# NXT.net
KiCad netlist of a schematic drawn in EAGLE
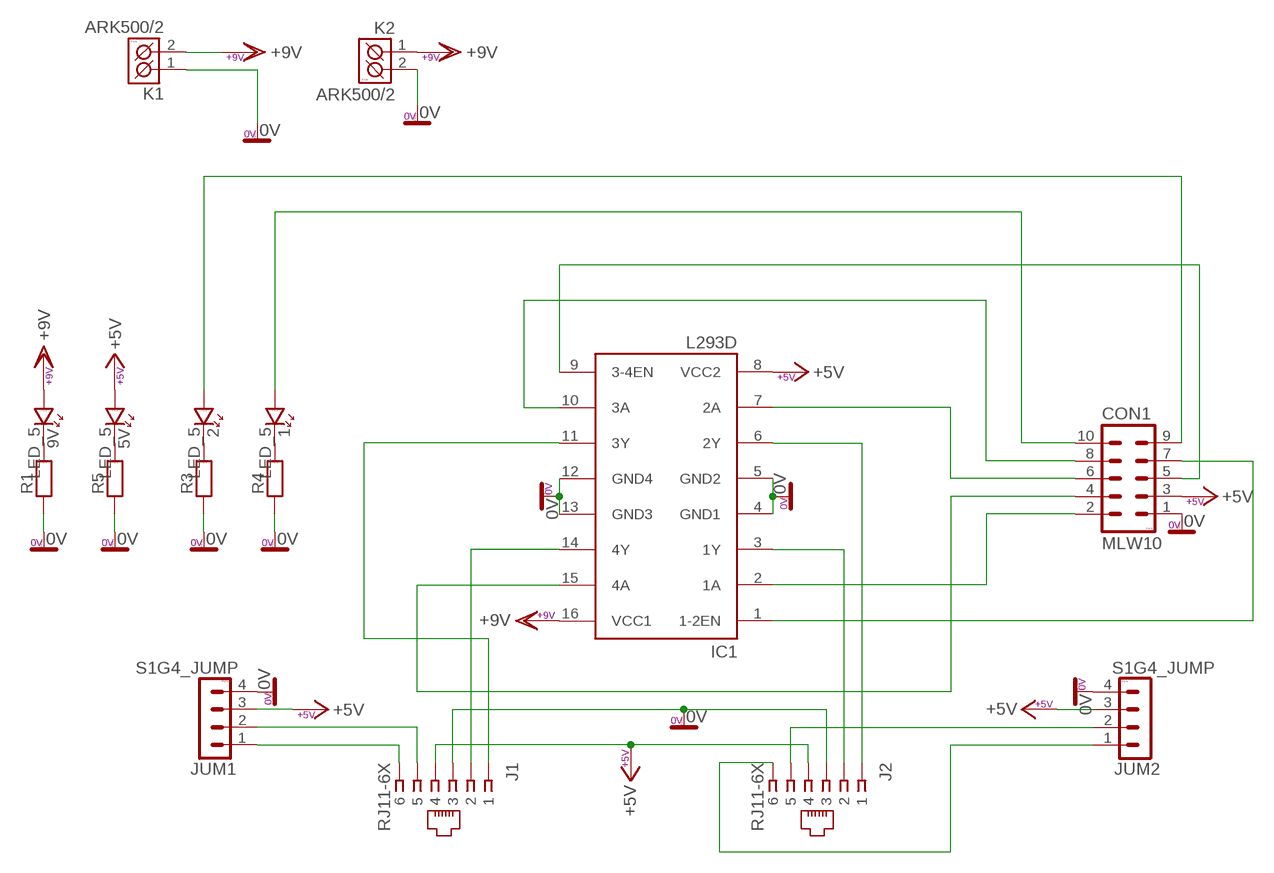
[diagram p0: schematic, sheet 1]

(export (version "E")
  (design (tool "Eeschema 10.0.6"))
  (components
    (comp (ref "1")
      (value "LED_5")
      (footprint "eagle-import:LED_5")
      (libsource (lib "eagle-import") (part "LED_5"))
    )
    (comp (ref "2")
      (value "LED_5")
      (footprint "eagle-import:LED_5")
      (libsource (lib "eagle-import") (part "LED_5"))
    )
    (comp (ref "5V")
      (value "LED_5")
      (footprint "eagle-import:LED_5")
      (libsource (lib "eagle-import") (part "LED_5"))
    )
    (comp (ref "9V")
      (value "LED_5")
      (footprint "eagle-import:LED_5")
      (libsource (lib "eagle-import") (part "LED_5"))
    )
    (comp (ref "CON1")
      (value "MLW10")
      (footprint "eagle-import:MLW10G")
      (libsource (lib "eagle-import") (part "MLW10"))
    )
    (comp (ref "IC1")
      (value "L293D")
      (footprint "eagle-import:DIL16")
      (libsource (lib "eagle-import") (part "L293D"))
    )
    (comp (ref "J1")
      (value "RJ11-6X")
      (footprint "eagle-import:RJ11-NO_SHIELD")
      (libsource (lib "eagle-import") (part "RJ11-6X"))
    )
    (comp (ref "J2")
      (value "RJ11-6X")
      (footprint "eagle-import:RJ11-NO_SHIELD")
      (libsource (lib "eagle-import") (part "RJ11-6X"))
    )
    (comp (ref "JUM1")
      (value "S1G4_JUMP")
      (footprint "eagle-import:S1G4_JUM")
      (libsource (lib "eagle-import") (part "S1G4_JUMP"))
    )
    (comp (ref "JUM2")
      (value "S1G4_JUMP")
      (footprint "eagle-import:S1G4_JUM")
      (libsource (lib "eagle-import") (part "S1G4_JUMP"))
    )
    (comp (ref "K1")
      (value "ARK500/2")
      (footprint "eagle-import:ARK500_2")
      (libsource (lib "eagle-import") (part "ARK500/2"))
    )
    (comp (ref "K2")
      (value "ARK500/2")
      (footprint "eagle-import:ARK500_2")
      (libsource (lib "eagle-import") (part "ARK500/2"))
    )
    (comp (ref "R1")
      (value "R_10")
      (footprint "eagle-import:R-10")
      (libsource (lib "eagle-import") (part "R_10"))
    )
    (comp (ref "R3")
      (value "R_10")
      (footprint "eagle-import:R-10")
      (libsource (lib "eagle-import") (part "R_10"))
    )
    (comp (ref "R4")
      (value "R_10")
      (footprint "eagle-import:R-10")
      (libsource (lib "eagle-import") (part "R_10"))
    )
    (comp (ref "R5")
      (value "R_10")
      (footprint "eagle-import:R-10")
      (libsource (lib "eagle-import") (part "R_10"))
    )
  )
  (nets
    (net (code "1") (name "+5V") (class "Default")
      (node (ref "5V") (pin "A") (pinfunction "A_A") (pintype "passive"))
      (node (ref "CON1") (pin "3") (pinfunction "3_3") (pintype "passive"))
      (node (ref "IC1") (pin "8") (pinfunction "VCC2_8") (pintype "power_in"))
      (node (ref "J1") (pin "4") (pinfunction "4_4") (pintype "passive"))
      (node (ref "J2") (pin "4") (pinfunction "4_4") (pintype "passive"))
      (node (ref "JUM1") (pin "3") (pinfunction "3_3") (pintype "passive"))
      (node (ref "JUM2") (pin "3") (pinfunction "3_3") (pintype "passive"))
    )
    (net (code "2") (name "+9V") (class "Default")
      (node (ref "9V") (pin "A") (pinfunction "A_A") (pintype "passive"))
      (node (ref "IC1") (pin "16") (pinfunction "VCC1_16") (pintype "power_in"))
      (node (ref "K1") (pin "2") (pinfunction "K2_2") (pintype "passive"))
      (node (ref "K2") (pin "1") (pinfunction "K1_1") (pintype "passive"))
    )
    (net (code "3") (name "0V") (class "Default")
      (node (ref "CON1") (pin "1") (pinfunction "1_1") (pintype "passive"))
      (node (ref "IC1") (pin "12") (pinfunction "GND4_12") (pintype "power_in"))
      (node (ref "IC1") (pin "13") (pinfunction "GND3_13") (pintype "power_in"))
      (node (ref "IC1") (pin "4") (pinfunction "GND1_4") (pintype "power_in"))
      (node (ref "IC1") (pin "5") (pinfunction "GND2_5") (pintype "power_in"))
      (node (ref "J1") (pin "3") (pinfunction "3_3") (pintype "passive"))
      (node (ref "J2") (pin "3") (pinfunction "3_3") (pintype "passive"))
      (node (ref "JUM1") (pin "4") (pinfunction "4_4") (pintype "passive"))
      (node (ref "JUM2") (pin "4") (pinfunction "4_4") (pintype "passive"))
      (node (ref "K1") (pin "1") (pinfunction "K1_1") (pintype "passive"))
      (node (ref "K2") (pin "2") (pinfunction "K2_2") (pintype "passive"))
      (node (ref "R1") (pin "1") (pinfunction "1_1") (pintype "passive"))
      (node (ref "R3") (pin "1") (pinfunction "1_1") (pintype "passive"))
      (node (ref "R4") (pin "1") (pinfunction "1_1") (pintype "passive"))
      (node (ref "R5") (pin "1") (pinfunction "1_1") (pintype "passive"))
    )
    (net (code "4") (name "Net-(1-PadA)") (class "Default")
      (node (ref "1") (pin "A") (pinfunction "A_A") (pintype "passive"))
      (node (ref "CON1") (pin "10") (pinfunction "10_10") (pintype "passive"))
    )
    (net (code "5") (name "Net-(1-PadK)") (class "Default")
      (node (ref "1") (pin "K") (pinfunction "K_K") (pintype "passive"))
      (node (ref "R4") (pin "2") (pinfunction "2_2") (pintype "passive"))
    )
    (net (code "6") (name "Net-(2-PadA)") (class "Default")
      (node (ref "2") (pin "A") (pinfunction "A_A") (pintype "passive"))
      (node (ref "CON1") (pin "9") (pinfunction "9_9") (pintype "passive"))
    )
    (net (code "7") (name "Net-(2-PadK)") (class "Default")
      (node (ref "2") (pin "K") (pinfunction "K_K") (pintype "passive"))
      (node (ref "R3") (pin "2") (pinfunction "2_2") (pintype "passive"))
    )
    (net (code "8") (name "Net-(5V-PadK)") (class "Default")
      (node (ref "5V") (pin "K") (pinfunction "K_K") (pintype "passive"))
      (node (ref "R5") (pin "2") (pinfunction "2_2") (pintype "passive"))
    )
    (net (code "9") (name "Net-(9V-PadK)") (class "Default")
      (node (ref "9V") (pin "K") (pinfunction "K_K") (pintype "passive"))
      (node (ref "R1") (pin "2") (pinfunction "2_2") (pintype "passive"))
    )
    (net (code "10") (name "Net-(IC1-1-2EN)") (class "Default")
      (node (ref "CON1") (pin "7") (pinfunction "7_7") (pintype "passive"))
      (node (ref "IC1") (pin "1") (pinfunction "1-2EN_1") (pintype "input"))
    )
    (net (code "11") (name "Net-(IC1-1A)") (class "Default")
      (node (ref "CON1") (pin "2") (pinfunction "2_2") (pintype "passive"))
      (node (ref "IC1") (pin "2") (pinfunction "1A_2") (pintype "input"))
    )
    (net (code "12") (name "Net-(IC1-1Y)") (class "Default")
      (node (ref "IC1") (pin "3") (pinfunction "1Y_3") (pintype "output"))
      (node (ref "J2") (pin "2") (pinfunction "2_2") (pintype "passive"))
    )
    (net (code "13") (name "Net-(IC1-2A)") (class "Default")
      (node (ref "CON1") (pin "6") (pinfunction "6_6") (pintype "passive"))
      (node (ref "IC1") (pin "7") (pinfunction "2A_7") (pintype "input"))
    )
    (net (code "14") (name "Net-(IC1-2Y)") (class "Default")
      (node (ref "IC1") (pin "6") (pinfunction "2Y_6") (pintype "output"))
      (node (ref "J2") (pin "1") (pinfunction "1_1") (pintype "passive"))
    )
    (net (code "15") (name "Net-(IC1-3-4EN)") (class "Default")
      (node (ref "CON1") (pin "5") (pinfunction "5_5") (pintype "passive"))
      (node (ref "IC1") (pin "9") (pinfunction "3-4EN_9") (pintype "input"))
    )
    (net (code "16") (name "Net-(IC1-3A)") (class "Default")
      (node (ref "CON1") (pin "8") (pinfunction "8_8") (pintype "passive"))
      (node (ref "IC1") (pin "10") (pinfunction "3A_10") (pintype "input"))
    )
    (net (code "17") (name "Net-(IC1-3Y)") (class "Default")
      (node (ref "IC1") (pin "11") (pinfunction "3Y_11") (pintype "output"))
      (node (ref "J1") (pin "1") (pinfunction "1_1") (pintype "passive"))
    )
    (net (code "18") (name "Net-(IC1-4A)") (class "Default")
      (node (ref "CON1") (pin "4") (pinfunction "4_4") (pintype "passive"))
      (node (ref "IC1") (pin "15") (pinfunction "4A_15") (pintype "input"))
    )
    (net (code "19") (name "Net-(IC1-4Y)") (class "Default")
      (node (ref "IC1") (pin "14") (pinfunction "4Y_14") (pintype "output"))
      (node (ref "J1") (pin "2") (pinfunction "2_2") (pintype "passive"))
    )
    (net (code "20") (name "Net-(J1-Pad5)") (class "Default")
      (node (ref "J1") (pin "5") (pinfunction "5_5") (pintype "passive"))
      (node (ref "JUM1") (pin "2") (pinfunction "2_2") (pintype "passive"))
    )
    (net (code "21") (name "Net-(J1-Pad6)") (class "Default")
      (node (ref "J1") (pin "6") (pinfunction "6_6") (pintype "passive"))
      (node (ref "JUM1") (pin "1") (pinfunction "1_1") (pintype "passive"))
    )
    (net (code "22") (name "Net-(J2-Pad5)") (class "Default")
      (node (ref "J2") (pin "5") (pinfunction "5_5") (pintype "passive"))
      (node (ref "JUM2") (pin "2") (pinfunction "2_2") (pintype "passive"))
    )
    (net (code "23") (name "Net-(J2-Pad6)") (class "Default")
      (node (ref "J2") (pin "6") (pinfunction "6_6") (pintype "passive"))
      (node (ref "JUM2") (pin "1") (pinfunction "1_1") (pintype "passive"))
    )
  )
)
